# PTN78000.net
KiCad netlist of a schematic drawn in EAGLE
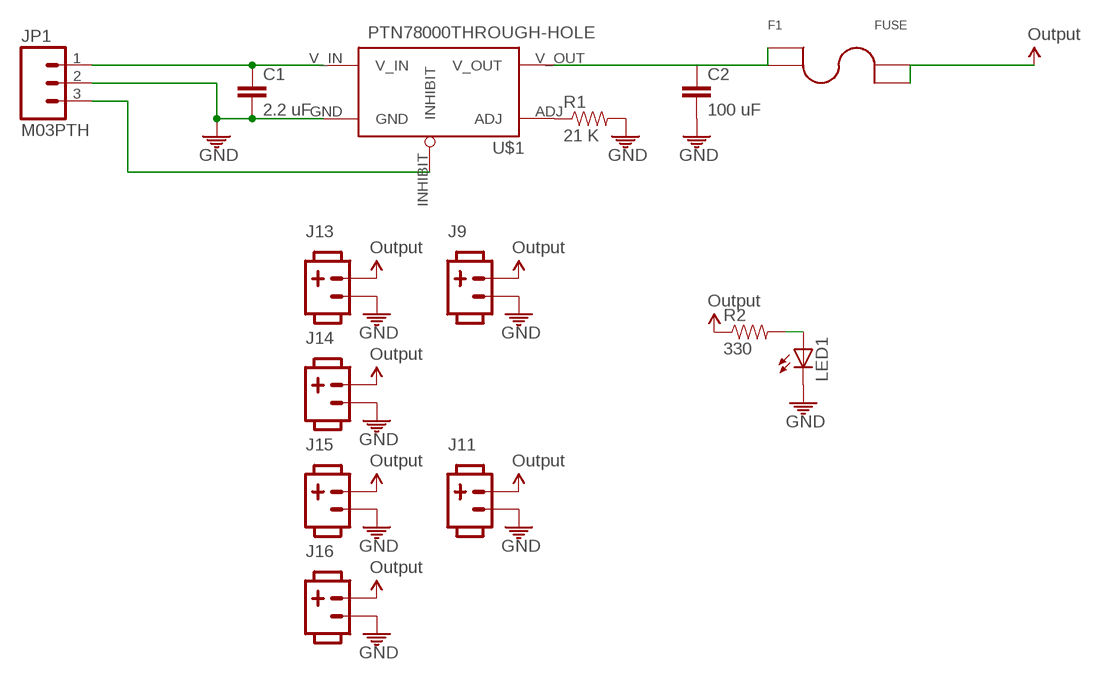
[diagram p0: schematic, sheet 1]

(export (version "E")
  (design (tool "Eeschema 10.0.6"))
  (components
    (comp (ref "C1")
      (value "2.2 uF")
      (footprint "eagle-import:1206")
      (libsource (lib "eagle-import") (part "CAP1206"))
    )
    (comp (ref "C2")
      (value "100 uF")
      (footprint "eagle-import:1206")
      (libsource (lib "eagle-import") (part "CAP1206"))
    )
    (comp (ref "F1")
      (value "FUSE")
      (footprint "eagle-import:FUSE_2AG")
      (libsource (lib "eagle-import") (part "FUSE"))
    )
    (comp (ref "J9")
      (value "POW_CONNECTFEMALE-RA")
      (footprint "eagle-import:SOCKET-FEMALE_RA-3.96MM-2")
      (libsource (lib "eagle-import") (part "POW_CONNECTFEMALE-RA"))
    )
    (comp (ref "J11")
      (value "POW_CONNECTFEMALE-RA")
      (footprint "eagle-import:SOCKET-FEMALE_RA-3.96MM-2")
      (libsource (lib "eagle-import") (part "POW_CONNECTFEMALE-RA"))
    )
    (comp (ref "J13")
      (value "POW_CONNECTFEMALE-RA")
      (footprint "eagle-import:SOCKET-FEMALE_RA-3.96MM-2")
      (libsource (lib "eagle-import") (part "POW_CONNECTFEMALE-RA"))
    )
    (comp (ref "J14")
      (value "POW_CONNECTFEMALE-RA")
      (footprint "eagle-import:SOCKET-FEMALE_RA-3.96MM-2")
      (libsource (lib "eagle-import") (part "POW_CONNECTFEMALE-RA"))
    )
    (comp (ref "J15")
      (value "POW_CONNECTFEMALE-RA")
      (footprint "eagle-import:SOCKET-FEMALE_RA-3.96MM-2")
      (libsource (lib "eagle-import") (part "POW_CONNECTFEMALE-RA"))
    )
    (comp (ref "J16")
      (value "POW_CONNECTFEMALE-RA")
      (footprint "eagle-import:SOCKET-FEMALE_RA-3.96MM-2")
      (libsource (lib "eagle-import") (part "POW_CONNECTFEMALE-RA"))
    )
    (comp (ref "JP1")
      (value "M03PTH")
      (footprint "eagle-import:1X03")
      (libsource (lib "eagle-import") (part "M03PTH"))
    )
    (comp (ref "LED1")
      (value "LED5MM")
      (footprint "eagle-import:LED5MM")
      (libsource (lib "eagle-import") (part "LED5MM"))
    )
    (comp (ref "R1")
      (value "21 K")
      (footprint "eagle-import:1206")
      (libsource (lib "eagle-import") (part "RESISTOR1206"))
    )
    (comp (ref "R2")
      (value "330")
      (footprint "eagle-import:1206")
      (libsource (lib "eagle-import") (part "RESISTOR1206"))
    )
    (comp (ref "U$1")
      (value "PTN78000THROUGH-HOLE")
      (footprint "eagle-import:PTN78000")
      (libsource (lib "eagle-import") (part "PTN78000THROUGH-HOLE"))
    )
  )
  (nets
    (net (code "1") (name "GND") (class "Default")
      (node (ref "C1") (pin "2") (pinfunction "2_2") (pintype "passive"))
      (node (ref "C2") (pin "2") (pinfunction "2_2") (pintype "passive"))
      (node (ref "J11") (pin "2") (pinfunction "2_2") (pintype "passive"))
      (node (ref "J13") (pin "2") (pinfunction "2_2") (pintype "passive"))
      (node (ref "J14") (pin "2") (pinfunction "2_2") (pintype "passive"))
      (node (ref "J15") (pin "2") (pinfunction "2_2") (pintype "passive"))
      (node (ref "J16") (pin "2") (pinfunction "2_2") (pintype "passive"))
      (node (ref "J9") (pin "2") (pinfunction "2_2") (pintype "passive"))
      (node (ref "JP1") (pin "2") (pinfunction "2_2") (pintype "passive"))
      (node (ref "LED1") (pin "K") (pinfunction "C_K") (pintype "passive"))
      (node (ref "R1") (pin "2") (pinfunction "2_2") (pintype "passive"))
      (node (ref "U$1") (pin "GND") (pinfunction "GND_GND") (pintype "power_in"))
    )
    (net (code "2") (name "Net-(C1-Pad1)") (class "Default")
      (node (ref "C1") (pin "1") (pinfunction "1_1") (pintype "passive"))
      (node (ref "JP1") (pin "1") (pinfunction "1_1") (pintype "passive"))
      (node (ref "U$1") (pin "V_IN") (pinfunction "V_IN_V_IN") (pintype "power_in"))
    )
    (net (code "3") (name "Net-(F1-1)") (class "Default")
      (node (ref "C2") (pin "1") (pinfunction "1_1") (pintype "passive"))
      (node (ref "F1") (pin "P$1") (pinfunction "1_P$1") (pintype "bidirectional"))
      (node (ref "F1") (pin "P$2") (pinfunction "2_P$2") (pintype "bidirectional"))
      (node (ref "U$1") (pin "V_OUT") (pinfunction "V_OUT_V_OUT") (pintype "output"))
    )
    (net (code "4") (name "Net-(JP1-Pad3)") (class "Default")
      (node (ref "JP1") (pin "3") (pinfunction "3_3") (pintype "passive"))
      (node (ref "U$1") (pin "INHIBIT") (pinfunction "INHIBIT_INHIBIT") (pintype "input"))
    )
    (net (code "5") (name "Net-(LED1-PadA)") (class "Default")
      (node (ref "LED1") (pin "A") (pinfunction "A_A") (pintype "passive"))
      (node (ref "R2") (pin "2") (pinfunction "2_2") (pintype "passive"))
    )
    (net (code "6") (name "Net-(R1-Pad1)") (class "Default")
      (node (ref "R1") (pin "1") (pinfunction "1_1") (pintype "passive"))
      (node (ref "U$1") (pin "ADJ") (pinfunction "ADJ_ADJ") (pintype "input"))
    )
    (net (code "7") (name "Output") (class "Default")
      (node (ref "F1") (pin "P$3") (pinfunction "3_P$3") (pintype "bidirectional"))
      (node (ref "F1") (pin "P$4") (pinfunction "4_P$4") (pintype "bidirectional"))
      (node (ref "J11") (pin "1") (pinfunction "1_1") (pintype "passive"))
      (node (ref "J13") (pin "1") (pinfunction "1_1") (pintype "passive"))
      (node (ref "J14") (pin "1") (pinfunction "1_1") (pintype "passive"))
      (node (ref "J15") (pin "1") (pinfunction "1_1") (pintype "passive"))
      (node (ref "J16") (pin "1") (pinfunction "1_1") (pintype "passive"))
      (node (ref "J9") (pin "1") (pinfunction "1_1") (pintype "passive"))
      (node (ref "R2") (pin "1") (pinfunction "1_1") (pintype "passive"))
    )
  )
)
